# Adafruit_NeoKey_1x4_QT_I2C.net
KiCad netlist of a schematic drawn in EAGLE
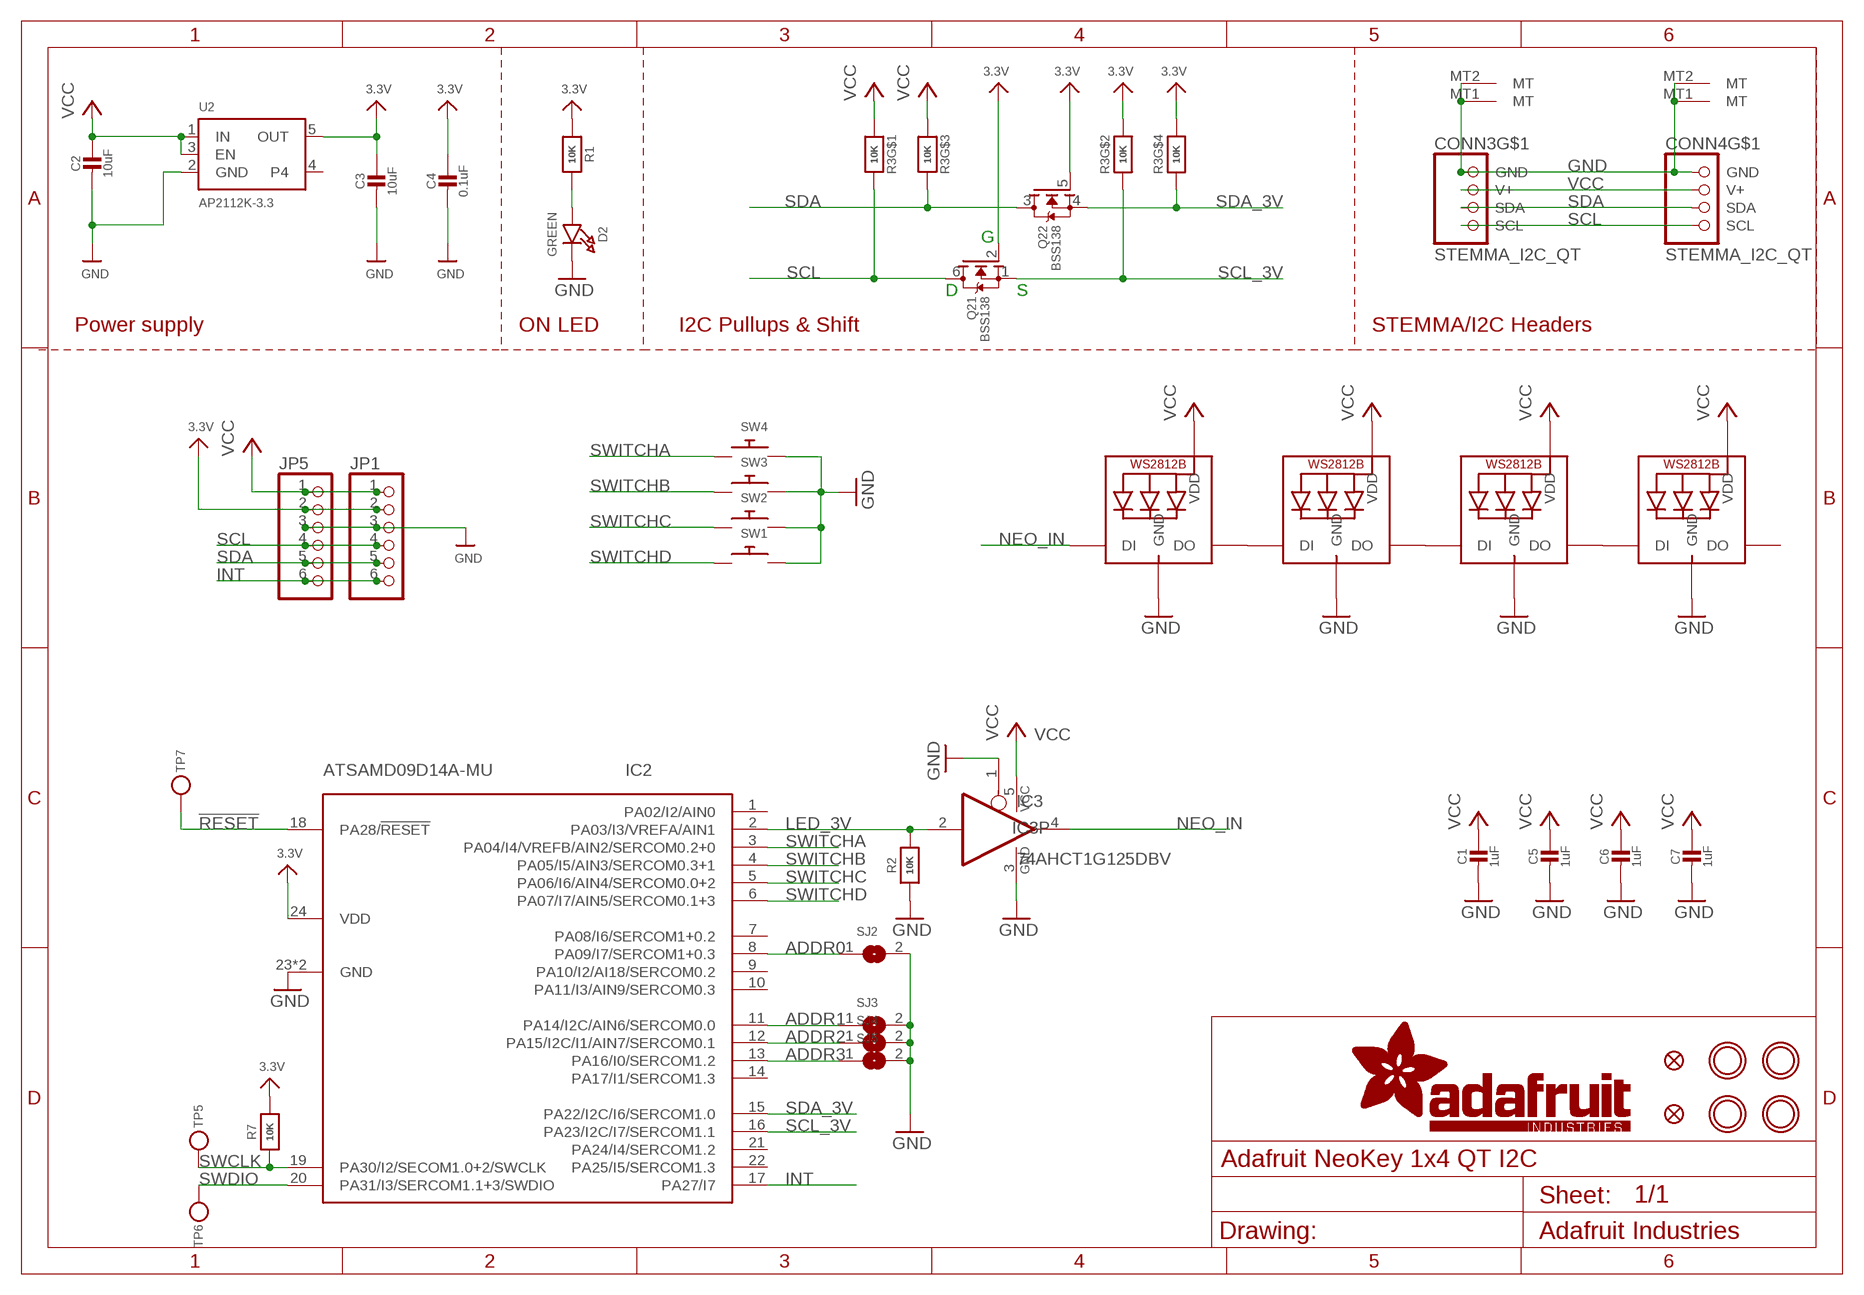
[diagram p0: schematic, sheet 1]

(export (version "E")
  (design (tool "Eeschema 10.0.6"))
  (components
    (comp (ref "C1")
      (value "1uF")
      (footprint "eagle-import:0603-NO")
      (libsource (lib "eagle-import") (part "CAP_CERAMIC0603_NO"))
    )
    (comp (ref "C2")
      (value "10uF")
      (footprint "eagle-import:0805-NO")
      (libsource (lib "eagle-import") (part "CAP_CERAMIC0805-NOOUTLINE"))
    )
    (comp (ref "C3")
      (value "10uF")
      (footprint "eagle-import:0805-NO")
      (libsource (lib "eagle-import") (part "CAP_CERAMIC0805-NOOUTLINE"))
    )
    (comp (ref "C4")
      (value "0.1uF")
      (footprint "eagle-import:0603-NO")
      (libsource (lib "eagle-import") (part "CAP_CERAMIC0603_NO"))
    )
    (comp (ref "C5")
      (value "1uF")
      (footprint "eagle-import:0603-NO")
      (libsource (lib "eagle-import") (part "CAP_CERAMIC0603_NO"))
    )
    (comp (ref "C6")
      (value "1uF")
      (footprint "eagle-import:0603-NO")
      (libsource (lib "eagle-import") (part "CAP_CERAMIC0603_NO"))
    )
    (comp (ref "C7")
      (value "1uF")
      (footprint "eagle-import:0603-NO")
      (libsource (lib "eagle-import") (part "CAP_CERAMIC0603_NO"))
    )
    (comp (ref "CONN3")
      (value "STEMMA_I2C_QT")
      (footprint "eagle-import:JST_SH4")
      (libsource (lib "eagle-import") (part "STEMMA_I2C_QT"))
    )
    (comp (ref "CONN4")
      (value "STEMMA_I2C_QT")
      (footprint "eagle-import:JST_SH4")
      (libsource (lib "eagle-import") (part "STEMMA_I2C_QT"))
    )
    (comp (ref "D2")
      (value "GREEN")
      (footprint "eagle-import:CHIPLED_0603_NOOUTLINE")
      (libsource (lib "eagle-import") (part "LED0603_NOOUTLINE"))
    )
    (comp (ref "FID1")
      (value "FIDUCIAL_1MM")
      (footprint "eagle-import:FIDUCIAL_1MM")
      (libsource (lib "eagle-import") (part "FIDUCIAL_1MM"))
    )
    (comp (ref "FID2")
      (value "FIDUCIAL_1MM")
      (footprint "eagle-import:FIDUCIAL_1MM")
      (libsource (lib "eagle-import") (part "FIDUCIAL_1MM"))
    )
    (comp (ref "IC2")
      (value "ATSAMD09D14A-MU")
      (footprint "eagle-import:QFN24_4MM")
      (libsource (lib "eagle-import") (part "ATSAMD09D14A-MU"))
    )
    (comp (ref "IC3")
      (value "74AHCT1G125DBV")
      (footprint "eagle-import:SOT23-5")
      (libsource (lib "eagle-import") (part "741G125DBVAHCT"))
    )
    (comp (ref "JP1")
      (value "HEADER-1X670MIL")
      (footprint "eagle-import:1X06_ROUND_70")
      (libsource (lib "eagle-import") (part "HEADER-1X670MIL"))
    )
    (comp (ref "JP5")
      (value "HEADER-1X670MIL")
      (footprint "eagle-import:1X06_ROUND_70")
      (libsource (lib "eagle-import") (part "HEADER-1X670MIL"))
    )
    (comp (ref "LED1")
      (value "WS2812B_SK6812E")
      (footprint "eagle-import:NEO3535_REVERSE")
      (libsource (lib "eagle-import") (part "WS2812B_SK6812E"))
    )
    (comp (ref "LED2")
      (value "WS2812B_SK6812E")
      (footprint "eagle-import:NEO3535_REVERSE")
      (libsource (lib "eagle-import") (part "WS2812B_SK6812E"))
    )
    (comp (ref "LED3")
      (value "WS2812B_SK6812E")
      (footprint "eagle-import:NEO3535_REVERSE")
      (libsource (lib "eagle-import") (part "WS2812B_SK6812E"))
    )
    (comp (ref "LED4")
      (value "WS2812B_SK6812E")
      (footprint "eagle-import:NEO3535_REVERSE")
      (libsource (lib "eagle-import") (part "WS2812B_SK6812E"))
    )
    (comp (ref "Q2")
      (value "BSS138")
      (footprint "eagle-import:SOT363")
      (libsource (lib "eagle-import") (part "MOSFET-N_DUAL"))
    )
    (comp (ref "R1")
      (value "10K")
      (footprint "eagle-import:0603-NO")
      (libsource (lib "eagle-import") (part "RESISTOR_0603_NOOUT"))
    )
    (comp (ref "R2")
      (value "10K")
      (footprint "eagle-import:0603-NO")
      (libsource (lib "eagle-import") (part "RESISTOR_0603_NOOUT"))
    )
    (comp (ref "R3")
      (value "10K")
      (footprint "eagle-import:RESPACK_4X0603")
      (libsource (lib "eagle-import") (part "RESISTOR_4PACK"))
    )
    (comp (ref "R7")
      (value "10K")
      (footprint "eagle-import:0603-NO")
      (libsource (lib "eagle-import") (part "RESISTOR_0603_NOOUT"))
    )
    (comp (ref "SJ2")
      (value "SOLDERJUMPER")
      (footprint "eagle-import:SOLDERJUMPER_ARROW_NOPASTE")
      (libsource (lib "eagle-import") (part "SOLDERJUMPER"))
    )
    (comp (ref "SJ3")
      (value "SOLDERJUMPER")
      (footprint "eagle-import:SOLDERJUMPER_ARROW_NOPASTE")
      (libsource (lib "eagle-import") (part "SOLDERJUMPER"))
    )
    (comp (ref "SJ4")
      (value "SOLDERJUMPER")
      (footprint "eagle-import:SOLDERJUMPER_ARROW_NOPASTE")
      (libsource (lib "eagle-import") (part "SOLDERJUMPER"))
    )
    (comp (ref "SJ5")
      (value "SOLDERJUMPER")
      (footprint "eagle-import:SOLDERJUMPER_ARROW_NOPASTE")
      (libsource (lib "eagle-import") (part "SOLDERJUMPER"))
    )
    (comp (ref "SW1")
      (value "SWITCH_PUSHBUTTON_KAILH_SOCKET")
      (footprint "eagle-import:KAILH_SOCKET")
      (libsource (lib "eagle-import") (part "SWITCH_PUSHBUTTON_KAILH_SOCKET"))
    )
    (comp (ref "SW2")
      (value "SWITCH_PUSHBUTTON_KAILH_SOCKET")
      (footprint "eagle-import:KAILH_SOCKET")
      (libsource (lib "eagle-import") (part "SWITCH_PUSHBUTTON_KAILH_SOCKET"))
    )
    (comp (ref "SW3")
      (value "SWITCH_PUSHBUTTON_KAILH_SOCKET")
      (footprint "eagle-import:KAILH_SOCKET")
      (libsource (lib "eagle-import") (part "SWITCH_PUSHBUTTON_KAILH_SOCKET"))
    )
    (comp (ref "SW4")
      (value "SWITCH_PUSHBUTTON_KAILH_SOCKET")
      (footprint "eagle-import:KAILH_SOCKET")
      (libsource (lib "eagle-import") (part "SWITCH_PUSHBUTTON_KAILH_SOCKET"))
    )
    (comp (ref "TP5")
      (value "TESTPOINTROUND1.5MM")
      (footprint "eagle-import:TESTPOINT_ROUND_1.5MM")
      (libsource (lib "eagle-import") (part "TESTPOINTROUND1.5MM"))
    )
    (comp (ref "TP6")
      (value "TESTPOINTROUND1.5MM")
      (footprint "eagle-import:TESTPOINT_ROUND_1.5MM")
      (libsource (lib "eagle-import") (part "TESTPOINTROUND1.5MM"))
    )
    (comp (ref "TP7")
      (value "TESTPOINTROUND1.5MM")
      (footprint "eagle-import:TESTPOINT_ROUND_1.5MM")
      (libsource (lib "eagle-import") (part "TESTPOINTROUND1.5MM"))
    )
    (comp (ref "U$3")
      (value "MOUNTINGHOLE2.5")
      (footprint "eagle-import:MOUNTINGHOLE_2.5_PLATED")
      (libsource (lib "eagle-import") (part "MOUNTINGHOLE2.5"))
    )
    (comp (ref "U$17")
      (value "MOUNTINGHOLE2.5")
      (footprint "eagle-import:MOUNTINGHOLE_2.5_PLATED")
      (libsource (lib "eagle-import") (part "MOUNTINGHOLE2.5"))
    )
    (comp (ref "U$19")
      (value "MOUNTINGHOLE2.5")
      (footprint "eagle-import:MOUNTINGHOLE_2.5_PLATED")
      (libsource (lib "eagle-import") (part "MOUNTINGHOLE2.5"))
    )
    (comp (ref "U$21")
      (value "MOUNTINGHOLE2.5")
      (footprint "eagle-import:MOUNTINGHOLE_2.5_PLATED")
      (libsource (lib "eagle-import") (part "MOUNTINGHOLE2.5"))
    )
    (comp (ref "U2")
      (value "AP2112K-3.3")
      (footprint "eagle-import:SOT23-5")
      (libsource (lib "eagle-import") (part "VREG_SOT23-5"))
    )
  )
  (nets
    (net (code "1") (name "/ADDR0") (class "Default")
      (node (ref "IC2") (pin "8") (pinfunction "PA09/I7/SERCOM1+0.3_8") (pintype "bidirectional"))
      (node (ref "SJ2") (pin "1") (pinfunction "1_1") (pintype "passive"))
    )
    (net (code "2") (name "/ADDR1") (class "Default")
      (node (ref "IC2") (pin "11") (pinfunction "PA14/I2C/AIN6/SERCOM0.0_11") (pintype "bidirectional"))
      (node (ref "SJ3") (pin "1") (pinfunction "1_1") (pintype "passive"))
    )
    (net (code "3") (name "/ADDR2") (class "Default")
      (node (ref "IC2") (pin "12") (pinfunction "PA15/I2C/I1/AIN7/SERCOM0.1_12") (pintype "bidirectional"))
      (node (ref "SJ4") (pin "1") (pinfunction "1_1") (pintype "passive"))
    )
    (net (code "4") (name "/ADDR3") (class "Default")
      (node (ref "IC2") (pin "13") (pinfunction "PA16/I0/SERCOM1.2_13") (pintype "bidirectional"))
      (node (ref "SJ5") (pin "1") (pinfunction "1_1") (pintype "passive"))
    )
    (net (code "5") (name "/INT") (class "Default")
      (node (ref "IC2") (pin "17") (pinfunction "PA27/I7_17") (pintype "bidirectional"))
      (node (ref "JP1") (pin "6") (pinfunction "6_6") (pintype "passive"))
      (node (ref "JP5") (pin "6") (pinfunction "6_6") (pintype "passive"))
    )
    (net (code "6") (name "/LED_3V") (class "Default")
      (node (ref "IC2") (pin "2") (pinfunction "PA03/I3/VREFA/AIN1_2") (pintype "bidirectional"))
      (node (ref "IC3") (pin "2") (pinfunction "I_2") (pintype "input"))
      (node (ref "R2") (pin "2") (pinfunction "2_2") (pintype "passive"))
    )
    (net (code "7") (name "/NEO_IN") (class "Default")
      (node (ref "IC3") (pin "4") (pinfunction "O_4") (pintype "tri_state"))
      (node (ref "LED1") (pin "4-DIN") (pinfunction "DI_4-DIN") (pintype "input"))
    )
    (net (code "8") (name "/SCL") (class "Default")
      (node (ref "CONN3") (pin "4") (pinfunction "SCL_4") (pintype "passive"))
      (node (ref "CONN4") (pin "4") (pinfunction "SCL_4") (pintype "passive"))
      (node (ref "JP1") (pin "4") (pinfunction "4_4") (pintype "passive"))
      (node (ref "JP5") (pin "4") (pinfunction "4_4") (pintype "passive"))
      (node (ref "Q2") (pin "6") (pinfunction "D_6") (pintype "bidirectional"))
      (node (ref "R3") (pin "8") (pinfunction "2_8") (pintype "passive"))
    )
    (net (code "9") (name "/SCL_3V") (class "Default")
      (node (ref "IC2") (pin "16") (pinfunction "PA23/I2C/I7/SERCOM1.1_16") (pintype "bidirectional"))
      (node (ref "Q2") (pin "1") (pinfunction "S_1") (pintype "bidirectional"))
      (node (ref "R3") (pin "7") (pinfunction "2_7") (pintype "passive"))
    )
    (net (code "10") (name "/SDA") (class "Default")
      (node (ref "CONN3") (pin "3") (pinfunction "SDA_3") (pintype "passive"))
      (node (ref "CONN4") (pin "3") (pinfunction "SDA_3") (pintype "passive"))
      (node (ref "JP1") (pin "5") (pinfunction "5_5") (pintype "passive"))
      (node (ref "JP5") (pin "5") (pinfunction "5_5") (pintype "passive"))
      (node (ref "Q2") (pin "3") (pinfunction "D_3") (pintype "bidirectional"))
      (node (ref "R3") (pin "6") (pinfunction "2_6") (pintype "passive"))
    )
    (net (code "11") (name "/SDA_3V") (class "Default")
      (node (ref "IC2") (pin "15") (pinfunction "PA22/I2C/I6/SERCOM1.0_15") (pintype "bidirectional"))
      (node (ref "Q2") (pin "4") (pinfunction "S_4") (pintype "bidirectional"))
      (node (ref "R3") (pin "5") (pinfunction "2_5") (pintype "passive"))
    )
    (net (code "12") (name "/SWCLK") (class "Default")
      (node (ref "IC2") (pin "19") (pinfunction "PA30/I2/SECOM1.0+2/SWCLK_19") (pintype "bidirectional"))
      (node (ref "R7") (pin "1") (pinfunction "1_1") (pintype "passive"))
      (node (ref "TP5") (pin "P$1") (pinfunction "P$1_P$1") (pintype "bidirectional"))
    )
    (net (code "13") (name "/SWDIO") (class "Default")
      (node (ref "IC2") (pin "20") (pinfunction "PA31/I3/SERCOM1.1+3/SWDIO_20") (pintype "bidirectional"))
      (node (ref "TP6") (pin "P$1") (pinfunction "P$1_P$1") (pintype "bidirectional"))
    )
    (net (code "14") (name "/SWITCHA") (class "Default")
      (node (ref "IC2") (pin "3") (pinfunction "PA04/I4/VREFB/AIN2/SERCOM0.2+0_3") (pintype "bidirectional"))
      (node (ref "SW4") (pin "2") (pinfunction "P$2_2") (pintype "passive"))
    )
    (net (code "15") (name "/SWITCHB") (class "Default")
      (node (ref "IC2") (pin "4") (pinfunction "PA05/I5/AIN3/SERCOM0.3+1_4") (pintype "bidirectional"))
      (node (ref "SW3") (pin "2") (pinfunction "P$2_2") (pintype "passive"))
    )
    (net (code "16") (name "/SWITCHC") (class "Default")
      (node (ref "IC2") (pin "5") (pinfunction "PA06/I6/AIN4/SERCOM0.0+2_5") (pintype "bidirectional"))
      (node (ref "SW2") (pin "2") (pinfunction "P$2_2") (pintype "passive"))
    )
    (net (code "17") (name "/SWITCHD") (class "Default")
      (node (ref "IC2") (pin "6") (pinfunction "PA07/I7/AIN5/SERCOM0.1+3_6") (pintype "bidirectional"))
      (node (ref "SW1") (pin "2") (pinfunction "P$2_2") (pintype "passive"))
    )
    (net (code "18") (name "/~{RESET}") (class "Default")
      (node (ref "IC2") (pin "18") (pinfunction "PA28/~{RESET}_18") (pintype "bidirectional"))
      (node (ref "TP7") (pin "P$1") (pinfunction "P$1_P$1") (pintype "bidirectional"))
    )
    (net (code "19") (name "3.3V") (class "Default")
      (node (ref "C3") (pin "1") (pinfunction "1_1") (pintype "passive"))
      (node (ref "C4") (pin "1") (pinfunction "1_1") (pintype "passive"))
      (node (ref "IC2") (pin "24") (pinfunction "VDD_24") (pintype "power_in"))
      (node (ref "JP1") (pin "2") (pinfunction "2_2") (pintype "passive"))
      (node (ref "JP5") (pin "2") (pinfunction "2_2") (pintype "passive"))
      (node (ref "Q2") (pin "2") (pinfunction "G_2") (pintype "bidirectional"))
      (node (ref "Q2") (pin "5") (pinfunction "G_5") (pintype "bidirectional"))
      (node (ref "R1") (pin "1") (pinfunction "1_1") (pintype "passive"))
      (node (ref "R3") (pin "2") (pinfunction "1_2") (pintype "passive"))
      (node (ref "R3") (pin "4") (pinfunction "1_4") (pintype "passive"))
      (node (ref "R7") (pin "2") (pinfunction "2_2") (pintype "passive"))
      (node (ref "U2") (pin "5") (pinfunction "OUT_5") (pintype "power_in"))
    )
    (net (code "20") (name "GND") (class "Default")
      (node (ref "C1") (pin "2") (pinfunction "2_2") (pintype "passive"))
      (node (ref "C2") (pin "2") (pinfunction "2_2") (pintype "passive"))
      (node (ref "C3") (pin "2") (pinfunction "2_2") (pintype "passive"))
      (node (ref "C4") (pin "2") (pinfunction "2_2") (pintype "passive"))
      (node (ref "C5") (pin "2") (pinfunction "2_2") (pintype "passive"))
      (node (ref "C6") (pin "2") (pinfunction "2_2") (pintype "passive"))
      (node (ref "C7") (pin "2") (pinfunction "2_2") (pintype "passive"))
      (node (ref "CONN3") (pin "1") (pinfunction "GND_1") (pintype "passive"))
      (node (ref "CONN3") (pin "MT1") (pinfunction "MT_MT1") (pintype "bidirectional"))
      (node (ref "CONN3") (pin "MT2") (pinfunction "MT_MT2") (pintype "bidirectional"))
      (node (ref "CONN4") (pin "1") (pinfunction "GND_1") (pintype "passive"))
      (node (ref "CONN4") (pin "MT1") (pinfunction "MT_MT1") (pintype "bidirectional"))
      (node (ref "CONN4") (pin "MT2") (pinfunction "MT_MT2") (pintype "bidirectional"))
      (node (ref "D2") (pin "C") (pinfunction "C_C") (pintype "passive"))
      (node (ref "IC2") (pin "23") (pinfunction "GND_23") (pintype "power_in"))
      (node (ref "IC2") (pin "THERM") (pinfunction "GND_THERM") (pintype "power_in"))
      (node (ref "IC3") (pin "1") (pinfunction "OE_1") (pintype "input"))
      (node (ref "IC3") (pin "3") (pinfunction "GND_3") (pintype "power_in"))
      (node (ref "JP1") (pin "3") (pinfunction "3_3") (pintype "passive"))
      (node (ref "JP5") (pin "3") (pinfunction "3_3") (pintype "passive"))
      (node (ref "LED1") (pin "3-GND") (pinfunction "GND_3-GND") (pintype "power_in"))
      (node (ref "LED2") (pin "3-GND") (pinfunction "GND_3-GND") (pintype "power_in"))
      (node (ref "LED3") (pin "3-GND") (pinfunction "GND_3-GND") (pintype "power_in"))
      (node (ref "LED4") (pin "3-GND") (pinfunction "GND_3-GND") (pintype "power_in"))
      (node (ref "R2") (pin "1") (pinfunction "1_1") (pintype "passive"))
      (node (ref "SJ2") (pin "2") (pinfunction "2_2") (pintype "passive"))
      (node (ref "SJ3") (pin "2") (pinfunction "2_2") (pintype "passive"))
      (node (ref "SJ4") (pin "2") (pinfunction "2_2") (pintype "passive"))
      (node (ref "SJ5") (pin "2") (pinfunction "2_2") (pintype "passive"))
      (node (ref "SW1") (pin "1") (pinfunction "P$1_1") (pintype "passive"))
      (node (ref "SW2") (pin "1") (pinfunction "P$1_1") (pintype "passive"))
      (node (ref "SW3") (pin "1") (pinfunction "P$1_1") (pintype "passive"))
      (node (ref "SW4") (pin "1") (pinfunction "P$1_1") (pintype "passive"))
      (node (ref "U2") (pin "2") (pinfunction "GND_2") (pintype "power_in"))
    )
    (net (code "21") (name "Net-(D2-PadA)") (class "Default")
      (node (ref "D2") (pin "A") (pinfunction "A_A") (pintype "passive"))
      (node (ref "R1") (pin "2") (pinfunction "2_2") (pintype "passive"))
    )
    (net (code "22") (name "Net-(LED1-DO)") (class "Default")
      (node (ref "LED1") (pin "2-DOUT") (pinfunction "DO_2-DOUT") (pintype "output"))
      (node (ref "LED2") (pin "4-DIN") (pinfunction "DI_4-DIN") (pintype "input"))
    )
    (net (code "23") (name "Net-(LED2-DO)") (class "Default")
      (node (ref "LED2") (pin "2-DOUT") (pinfunction "DO_2-DOUT") (pintype "output"))
      (node (ref "LED3") (pin "4-DIN") (pinfunction "DI_4-DIN") (pintype "input"))
    )
    (net (code "24") (name "Net-(LED3-DO)") (class "Default")
      (node (ref "LED3") (pin "2-DOUT") (pinfunction "DO_2-DOUT") (pintype "output"))
      (node (ref "LED4") (pin "4-DIN") (pinfunction "DI_4-DIN") (pintype "input"))
    )
    (net (code "25") (name "VCC") (class "Default")
      (node (ref "C1") (pin "1") (pinfunction "1_1") (pintype "passive"))
      (node (ref "C2") (pin "1") (pinfunction "1_1") (pintype "passive"))
      (node (ref "C5") (pin "1") (pinfunction "1_1") (pintype "passive"))
      (node (ref "C6") (pin "1") (pinfunction "1_1") (pintype "passive"))
      (node (ref "C7") (pin "1") (pinfunction "1_1") (pintype "passive"))
      (node (ref "CONN3") (pin "2") (pinfunction "V+_2") (pintype "passive"))
      (node (ref "CONN4") (pin "2") (pinfunction "V+_2") (pintype "passive"))
      (node (ref "IC3") (pin "5") (pinfunction "VCC_5") (pintype "power_in"))
      (node (ref "JP1") (pin "1") (pinfunction "1_1") (pintype "passive"))
      (node (ref "JP5") (pin "1") (pinfunction "1_1") (pintype "passive"))
      (node (ref "LED1") (pin "1-VDD") (pinfunction "VDD_1-VDD") (pintype "power_in"))
      (node (ref "LED2") (pin "1-VDD") (pinfunction "VDD_1-VDD") (pintype "power_in"))
      (node (ref "LED3") (pin "1-VDD") (pinfunction "VDD_1-VDD") (pintype "power_in"))
      (node (ref "LED4") (pin "1-VDD") (pinfunction "VDD_1-VDD") (pintype "power_in"))
      (node (ref "R3") (pin "1") (pinfunction "1_1") (pintype "passive"))
      (node (ref "R3") (pin "3") (pinfunction "1_3") (pintype "passive"))
      (node (ref "U2") (pin "1") (pinfunction "IN_1") (pintype "power_in"))
      (node (ref "U2") (pin "3") (pinfunction "EN_3") (pintype "input"))
    )
    (net (code "26") (name "unconnected-(IC2-PA02{slash}I2{slash}AIN0-Pad1)") (class "Default")
      (node (ref "IC2") (pin "1") (pinfunction "PA02/I2/AIN0_1") (pintype "bidirectional"))
    )
    (net (code "27") (name "unconnected-(IC2-PA08{slash}I6{slash}SERCOM1+0.2-Pad7)") (class "Default")
      (node (ref "IC2") (pin "7") (pinfunction "PA08/I6/SERCOM1+0.2_7") (pintype "bidirectional"))
    )
    (net (code "28") (name "unconnected-(IC2-PA10{slash}I2{slash}AI18{slash}SERCOM0.2-Pad9)") (class "Default")
      (node (ref "IC2") (pin "9") (pinfunction "PA10/I2/AI18/SERCOM0.2_9") (pintype "bidirectional"))
    )
    (net (code "29") (name "unconnected-(IC2-PA11{slash}I3{slash}AIN9{slash}SERCOM0.3-Pad10)") (class "Default")
      (node (ref "IC2") (pin "10") (pinfunction "PA11/I3/AIN9/SERCOM0.3_10") (pintype "bidirectional"))
    )
    (net (code "30") (name "unconnected-(IC2-PA17{slash}I1{slash}SERCOM1.3-Pad14)") (class "Default")
      (node (ref "IC2") (pin "14") (pinfunction "PA17/I1/SERCOM1.3_14") (pintype "bidirectional"))
    )
    (net (code "31") (name "unconnected-(IC2-PA24{slash}I4{slash}SERCOM1.2-Pad21)") (class "Default")
      (node (ref "IC2") (pin "21") (pinfunction "PA24/I4/SERCOM1.2_21") (pintype "bidirectional"))
    )
    (net (code "32") (name "unconnected-(IC2-PA25{slash}I5{slash}SERCOM1.3-Pad22)") (class "Default")
      (node (ref "IC2") (pin "22") (pinfunction "PA25/I5/SERCOM1.3_22") (pintype "bidirectional"))
    )
    (net (code "33") (name "unconnected-(LED4-DO-Pad2-DOUT)") (class "Default")
      (node (ref "LED4") (pin "2-DOUT") (pinfunction "DO_2-DOUT") (pintype "output"))
    )
    (net (code "34") (name "unconnected-(U2-P4-Pad4)") (class "Default")
      (node (ref "U2") (pin "4") (pinfunction "P4_4") (pintype "bidirectional"))
    )
  )
)
